# WBD_03.net
KiCad netlist of a schematic drawn in EAGLE
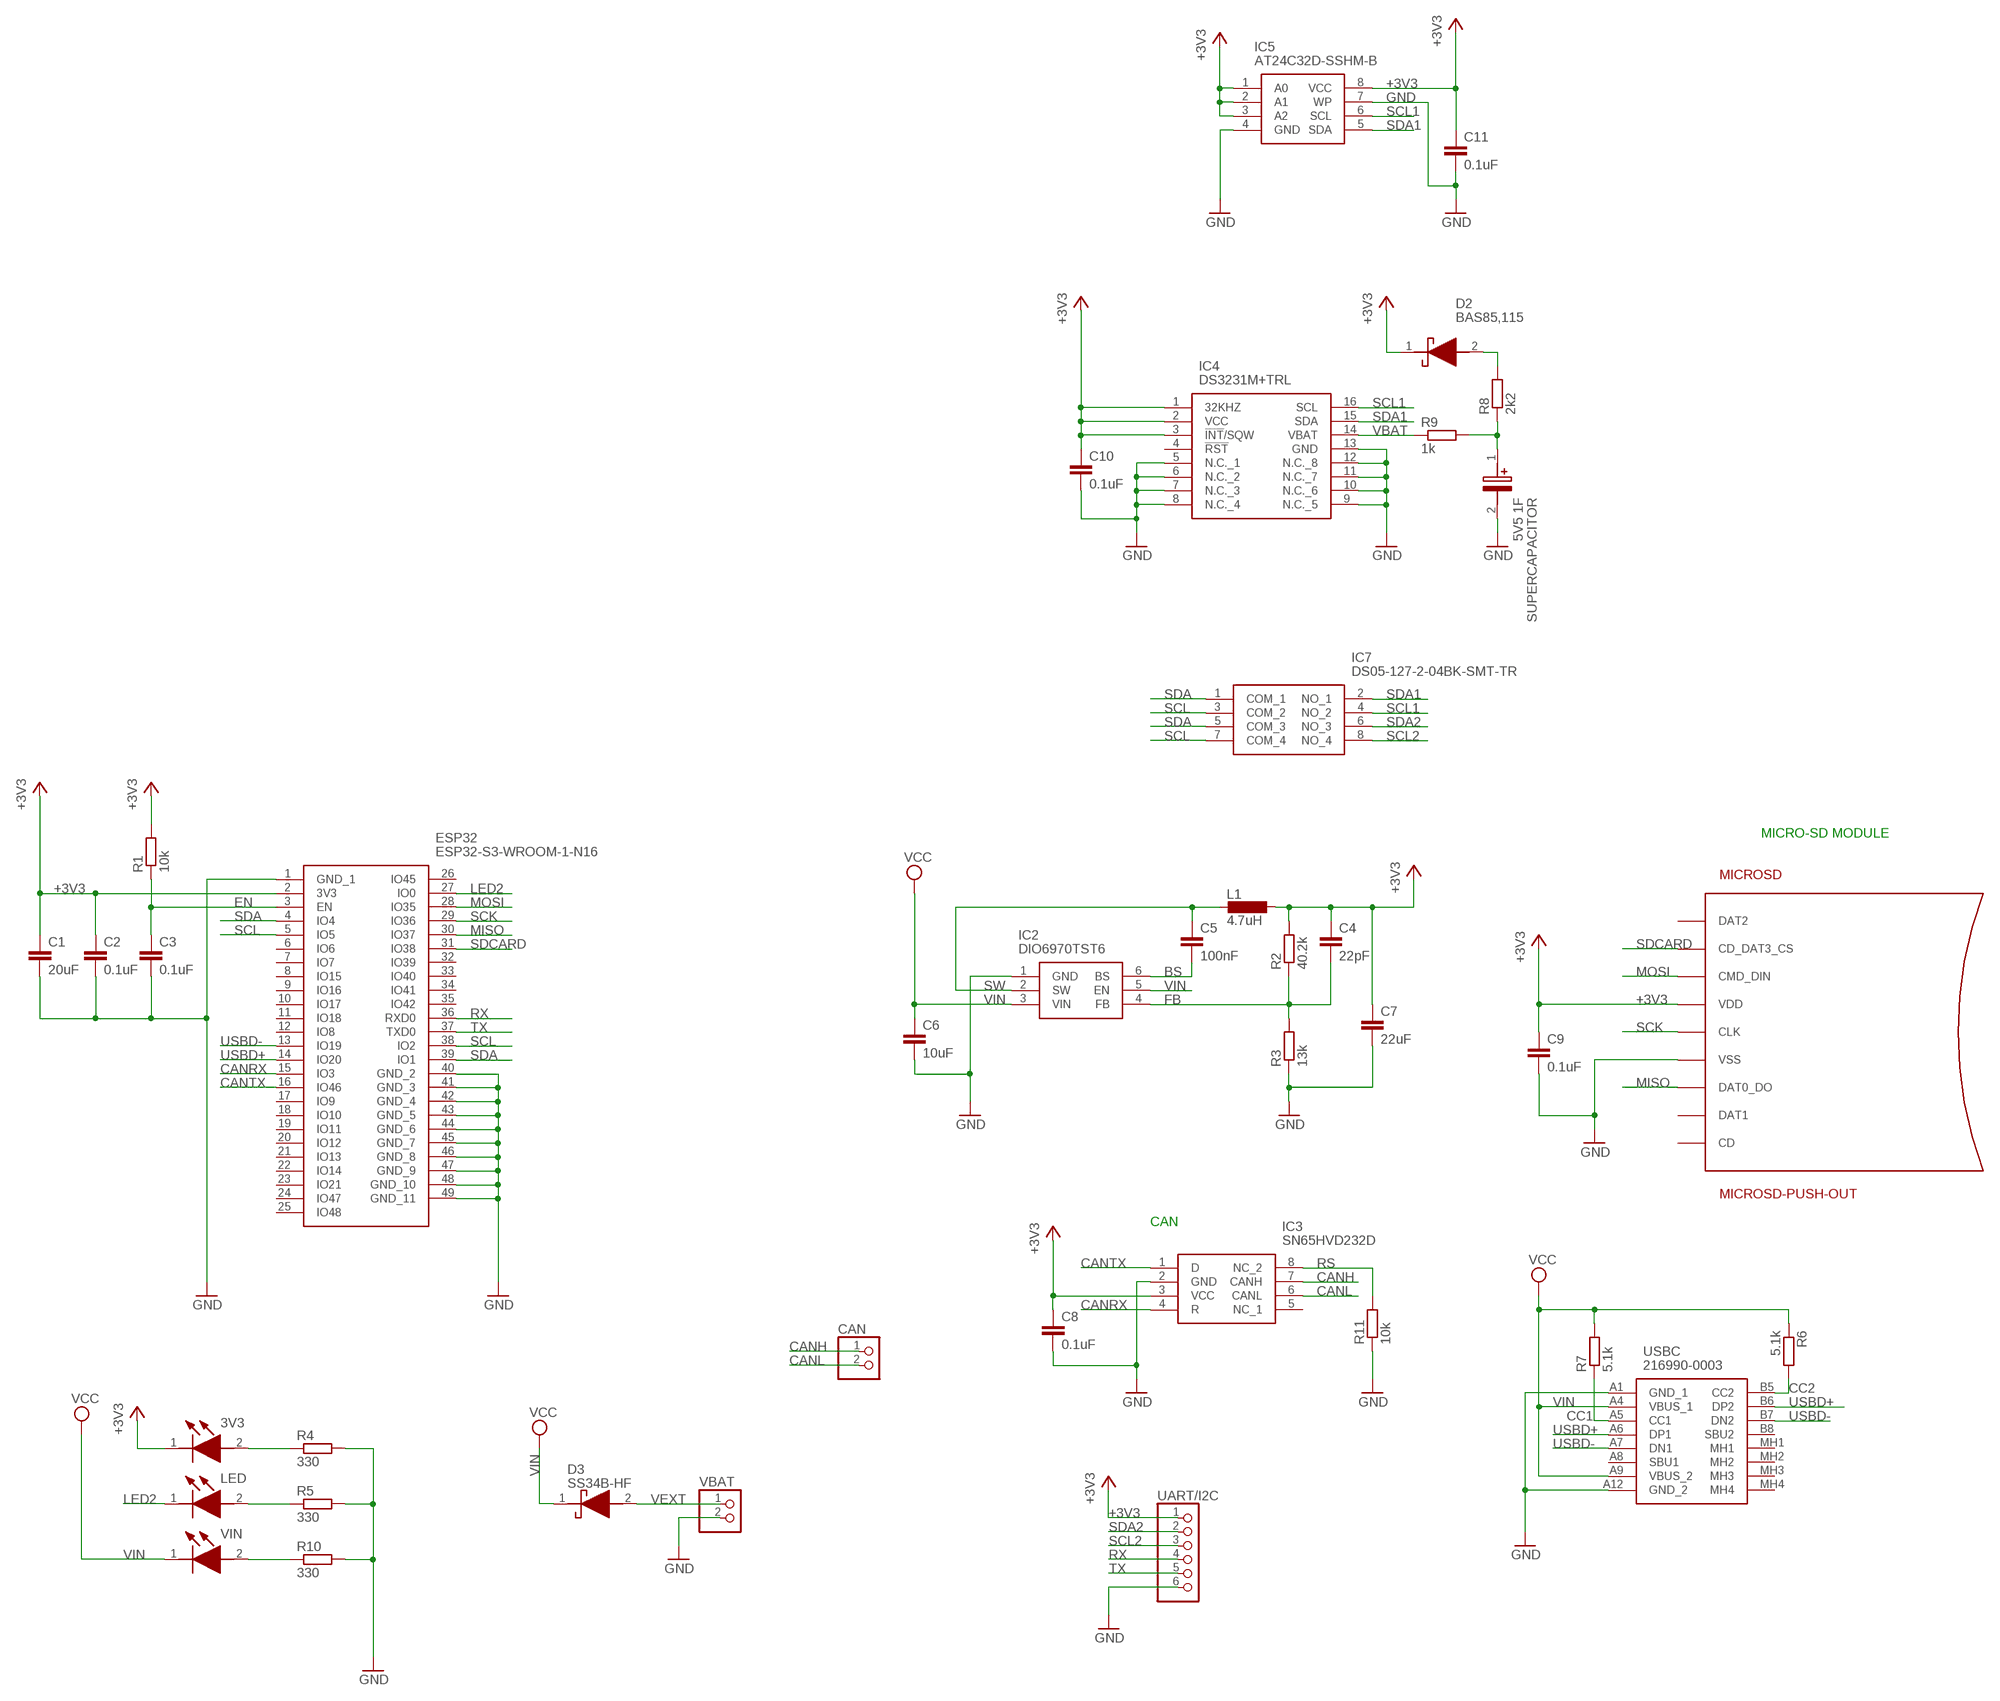
[diagram p0: schematic, sheet 1]

(export (version "E")
  (design (tool "Eeschema 10.0.6"))
  (components
    (comp (ref "3V3")
      (value "150060GS75000")
      (footprint "eagle-import:LEDC1608X80N")
      (fields (field (name "MOUSER_PART_NUMBER") "710-150060GS75000"))
      (libsource (lib "eagle-import") (part "150060GS75000"))
    )
    (comp (ref "C1")
      (value "20uF")
      (footprint "eagle-import:C0603")
      (libsource (lib "eagle-import") (part "C-EUC0603"))
    )
    (comp (ref "C2")
      (value "0.1uF")
      (footprint "eagle-import:C0603")
      (libsource (lib "eagle-import") (part "C-EUC0603"))
    )
    (comp (ref "C3")
      (value "0.1uF")
      (footprint "eagle-import:C0603")
      (libsource (lib "eagle-import") (part "C-EUC0603"))
    )
    (comp (ref "C4")
      (value "22pF")
      (footprint "eagle-import:C0603")
      (libsource (lib "eagle-import") (part "C-EUC0603"))
    )
    (comp (ref "C5")
      (value "100nF")
      (footprint "eagle-import:C0603")
      (libsource (lib "eagle-import") (part "C-EUC0603"))
    )
    (comp (ref "C6")
      (value "10uF")
      (footprint "eagle-import:C0603")
      (libsource (lib "eagle-import") (part "C-EUC0603"))
    )
    (comp (ref "C7")
      (value "22uF")
      (footprint "eagle-import:C0603")
      (libsource (lib "eagle-import") (part "C-EUC0603"))
    )
    (comp (ref "C8")
      (value "0.1uF")
      (footprint "eagle-import:C0603")
      (libsource (lib "eagle-import") (part "C-EUC0603"))
    )
    (comp (ref "C9")
      (value "0.1uF")
      (footprint "eagle-import:C0603")
      (libsource (lib "eagle-import") (part "C-EUC0603"))
    )
    (comp (ref "C10")
      (value "0.1uF")
      (footprint "eagle-import:C0603")
      (libsource (lib "eagle-import") (part "C-EUC0603"))
    )
    (comp (ref "C11")
      (value "0.1uF")
      (footprint "eagle-import:C0603")
      (libsource (lib "eagle-import") (part "C-EUC0603"))
    )
    (comp (ref "CAN")
      (value "PINHD-1X2")
      (footprint "eagle-import:1X02")
      (libsource (lib "eagle-import") (part "PINHD-1X2"))
    )
    (comp (ref "D2")
      (value "BAS85,115")
      (footprint "eagle-import:BAS85115")
      (fields (field (name "MOUSER_PART_NUMBER") "771-BAS85-T/R"))
      (libsource (lib "eagle-import") (part "BAS85,115"))
    )
    (comp (ref "D3")
      (value "SS34B-HF")
      (footprint "eagle-import:DIOM5336X320N")
      (fields (field (name "MOUSER_PART_NUMBER") "750-SS34B-HF"))
      (libsource (lib "eagle-import") (part "SS34B-HF"))
    )
    (comp (ref "ESP32")
      (value "ESP32-S3-WROOM-1-N16")
      (footprint "eagle-import:ESP32S3WROOM1N16")
      (fields (field (name "MOUSER_PART_NUMBER") "356-ESP32S3WROOM1N16"))
      (libsource (lib "eagle-import") (part "ESP32-S3-WROOM-1-N16"))
    )
    (comp (ref "IC2")
      (value "DIO6970TST6")
      (footprint "eagle-import:SOT95P280X90-6N")
      (fields (field (name "MOUSER_PART_NUMBER") "453-DIO6970ST6"))
      (libsource (lib "eagle-import") (part "DIO6970TST6"))
    )
    (comp (ref "IC3")
      (value "SN65HVD232D")
      (footprint "eagle-import:SOIC127P600X175-8N")
      (fields (field (name "MOUSER_PART_NUMBER") "595-SN65HVD232D"))
      (libsource (lib "eagle-import") (part "SN65HVD232D"))
    )
    (comp (ref "IC4")
      (value "DS3231M+TRL")
      (footprint "eagle-import:SOIC127P1032X265-16N")
      (fields (field (name "MOUSER_PART_NUMBER") "700-DS3231M+TRL"))
      (libsource (lib "eagle-import") (part "DS3231M+TRL"))
    )
    (comp (ref "IC5")
      (value "AT24C32D-SSHM-B")
      (footprint "eagle-import:SOIC127P600X175-8N")
      (fields (field (name "MOUSER_PART_NUMBER") "556-AT24C32D-SSHM-B"))
      (libsource (lib "eagle-import") (part "AT24C32D-SSHM-B"))
    )
    (comp (ref "IC7")
      (value "DS05-127-2-04BK-SMT-TR")
      (footprint "eagle-import:DS05127204BKSMTTR")
      (fields (field (name "MOUSER_PART_NUMBER") "490-DS05127204BK-STR"))
      (libsource (lib "eagle-import") (part "DS05-127-2-04BK-SMT-TR"))
    )
    (comp (ref "L1")
      (value "4.7uH")
      (footprint "eagle-import:L5650M")
      (libsource (lib "eagle-import") (part "L-EUL5650M"))
    )
    (comp (ref "LED")
      (value "150060GS75000")
      (footprint "eagle-import:LEDC1608X80N")
      (fields (field (name "MOUSER_PART_NUMBER") "710-150060GS75000"))
      (libsource (lib "eagle-import") (part "150060GS75000"))
    )
    (comp (ref "MICROSD")
      (value "MICROSD-PUSH-OUT")
      (footprint "eagle-import:MICROSD-PUSH-OUT")
      (libsource (lib "eagle-import") (part "MICROSD-PUSH-OUT"))
    )
    (comp (ref "R1")
      (value "10k")
      (footprint "eagle-import:R0603")
      (libsource (lib "eagle-import") (part "R-EU_R0603"))
    )
    (comp (ref "R2")
      (value "40.2k")
      (footprint "eagle-import:R0603")
      (libsource (lib "eagle-import") (part "R-EU_R0603"))
    )
    (comp (ref "R3")
      (value "13k")
      (footprint "eagle-import:R0603")
      (libsource (lib "eagle-import") (part "R-EU_R0603"))
    )
    (comp (ref "R4")
      (value "330")
      (footprint "eagle-import:R0603")
      (libsource (lib "eagle-import") (part "R-EU_R0603"))
    )
    (comp (ref "R5")
      (value "330")
      (footprint "eagle-import:R0603")
      (libsource (lib "eagle-import") (part "R-EU_R0603"))
    )
    (comp (ref "R6")
      (value "5.1k")
      (footprint "eagle-import:R0603")
      (libsource (lib "eagle-import") (part "R-EU_R0603"))
    )
    (comp (ref "R7")
      (value "5.1k")
      (footprint "eagle-import:R0603")
      (libsource (lib "eagle-import") (part "R-EU_R0603"))
    )
    (comp (ref "R8")
      (value "2k2")
      (footprint "eagle-import:R0603")
      (libsource (lib "eagle-import") (part "R-EU_R0603"))
    )
    (comp (ref "R9")
      (value "1k")
      (footprint "eagle-import:R0603")
      (libsource (lib "eagle-import") (part "R-EU_R0603"))
    )
    (comp (ref "R10")
      (value "330")
      (footprint "eagle-import:R0603")
      (libsource (lib "eagle-import") (part "R-EU_R0603"))
    )
    (comp (ref "R11")
      (value "10k")
      (footprint "eagle-import:R0603")
      (libsource (lib "eagle-import") (part "R-EU_R0603"))
    )
    (comp (ref "SUPERCAPACITOR")
      (value "5V5 1F")
      (footprint "eagle-import:CAPPRD500W130D2150H800")
      (fields
        (field (name "MANUFACTURER_PART_NUMBER") "DB-5R5D105T")
        (field (name "MOUSER_PART_NUMBER") "555-DB-5R5D105T")
      )
      (libsource (lib "eagle-import") (part "DB-5R5D105T"))
    )
    (comp (ref "UART/I2C")
      (value "PINHD-1X6")
      (footprint "eagle-import:1X06")
      (libsource (lib "eagle-import") (part "PINHD-1X6"))
    )
    (comp (ref "USBC")
      (value "216990-0003")
      (footprint "eagle-import:2169900003")
      (fields (field (name "MOUSER_PART_NUMBER") "538-216990-0003"))
      (libsource (lib "eagle-import") (part "216990-0003"))
    )
    (comp (ref "VBAT")
      (value "PINHD-1X2")
      (footprint "eagle-import:1X02")
      (libsource (lib "eagle-import") (part "PINHD-1X2"))
    )
    (comp (ref "VIN")
      (value "150060GS75000")
      (footprint "eagle-import:LEDC1608X80N")
      (fields (field (name "MOUSER_PART_NUMBER") "710-150060GS75000"))
      (libsource (lib "eagle-import") (part "150060GS75000"))
    )
  )
  (nets
    (net (code "1") (name "+3V3") (class "Default")
      (node (ref "3V3") (pin "1") (pinfunction "K_1") (pintype "bidirectional"))
      (node (ref "C1") (pin "1") (pinfunction "1_1") (pintype "passive"))
      (node (ref "C10") (pin "1") (pinfunction "1_1") (pintype "passive"))
      (node (ref "C11") (pin "1") (pinfunction "1_1") (pintype "passive"))
      (node (ref "C2") (pin "1") (pinfunction "1_1") (pintype "passive"))
      (node (ref "C4") (pin "1") (pinfunction "1_1") (pintype "passive"))
      (node (ref "C7") (pin "1") (pinfunction "1_1") (pintype "passive"))
      (node (ref "C8") (pin "1") (pinfunction "1_1") (pintype "passive"))
      (node (ref "C9") (pin "1") (pinfunction "1_1") (pintype "passive"))
      (node (ref "D2") (pin "1") (pinfunction "K_1") (pintype "bidirectional"))
      (node (ref "ESP32") (pin "2") (pinfunction "3V3_2") (pintype "bidirectional"))
      (node (ref "IC3") (pin "3") (pinfunction "VCC_3") (pintype "bidirectional"))
      (node (ref "IC4") (pin "1") (pinfunction "32KHZ_1") (pintype "bidirectional"))
      (node (ref "IC4") (pin "2") (pinfunction "VCC_2") (pintype "bidirectional"))
      (node (ref "IC4") (pin "3") (pinfunction "~{INT}/SQW_3") (pintype "bidirectional"))
      (node (ref "IC5") (pin "1") (pinfunction "A0_1") (pintype "bidirectional"))
      (node (ref "IC5") (pin "2") (pinfunction "A1_2") (pintype "bidirectional"))
      (node (ref "IC5") (pin "3") (pinfunction "A2_3") (pintype "bidirectional"))
      (node (ref "IC5") (pin "8") (pinfunction "VCC_8") (pintype "bidirectional"))
      (node (ref "L1") (pin "1") (pinfunction "1_1") (pintype "passive"))
      (node (ref "MICROSD") (pin "4") (pinfunction "VDD_4") (pintype "bidirectional"))
      (node (ref "R1") (pin "2") (pinfunction "2_2") (pintype "passive"))
      (node (ref "R2") (pin "2") (pinfunction "2_2") (pintype "passive"))
      (node (ref "UART/I2C") (pin "1") (pinfunction "1_1") (pintype "passive"))
    )
    (net (code "2") (name "/BS") (class "Default")
      (node (ref "C5") (pin "2") (pinfunction "2_2") (pintype "passive"))
      (node (ref "IC2") (pin "6") (pinfunction "BS_6") (pintype "bidirectional"))
    )
    (net (code "3") (name "/CANH") (class "Default")
      (node (ref "CAN") (pin "1") (pinfunction "1_1") (pintype "passive"))
      (node (ref "IC3") (pin "7") (pinfunction "CANH_7") (pintype "bidirectional"))
    )
    (net (code "4") (name "/CANL") (class "Default")
      (node (ref "CAN") (pin "2") (pinfunction "2_2") (pintype "passive"))
      (node (ref "IC3") (pin "6") (pinfunction "CANL_6") (pintype "bidirectional"))
    )
    (net (code "5") (name "/CANRX") (class "Default")
      (node (ref "ESP32") (pin "15") (pinfunction "IO3_15") (pintype "bidirectional"))
      (node (ref "IC3") (pin "4") (pinfunction "R_4") (pintype "bidirectional"))
    )
    (net (code "6") (name "/CANTX") (class "Default")
      (node (ref "ESP32") (pin "16") (pinfunction "IO46_16") (pintype "bidirectional"))
      (node (ref "IC3") (pin "1") (pinfunction "D_1") (pintype "bidirectional"))
    )
    (net (code "7") (name "/CC1") (class "Default")
      (node (ref "R7") (pin "1") (pinfunction "1_1") (pintype "passive"))
      (node (ref "USBC") (pin "A5") (pinfunction "CC1_A5") (pintype "bidirectional"))
    )
    (net (code "8") (name "/CC2") (class "Default")
      (node (ref "R6") (pin "2") (pinfunction "2_2") (pintype "passive"))
      (node (ref "USBC") (pin "B5") (pinfunction "CC2_B5") (pintype "bidirectional"))
    )
    (net (code "9") (name "/EN") (class "Default")
      (node (ref "C3") (pin "1") (pinfunction "1_1") (pintype "passive"))
      (node (ref "ESP32") (pin "3") (pinfunction "EN_3") (pintype "bidirectional"))
      (node (ref "R1") (pin "1") (pinfunction "1_1") (pintype "passive"))
    )
    (net (code "10") (name "/FB") (class "Default")
      (node (ref "C4") (pin "2") (pinfunction "2_2") (pintype "passive"))
      (node (ref "IC2") (pin "4") (pinfunction "FB_4") (pintype "bidirectional"))
      (node (ref "R2") (pin "1") (pinfunction "1_1") (pintype "passive"))
      (node (ref "R3") (pin "2") (pinfunction "2_2") (pintype "passive"))
    )
    (net (code "11") (name "/LED2") (class "Default")
      (node (ref "ESP32") (pin "27") (pinfunction "IO0_27") (pintype "bidirectional"))
      (node (ref "LED") (pin "1") (pinfunction "K_1") (pintype "bidirectional"))
    )
    (net (code "12") (name "/MISO") (class "Default")
      (node (ref "ESP32") (pin "30") (pinfunction "IO37_30") (pintype "bidirectional"))
      (node (ref "MICROSD") (pin "7") (pinfunction "DAT0_DO_7") (pintype "bidirectional"))
    )
    (net (code "13") (name "/MOSI") (class "Default")
      (node (ref "ESP32") (pin "28") (pinfunction "IO35_28") (pintype "bidirectional"))
      (node (ref "MICROSD") (pin "3") (pinfunction "CMD_DIN_3") (pintype "bidirectional"))
    )
    (net (code "14") (name "/RS") (class "Default")
      (node (ref "IC3") (pin "8") (pinfunction "NC_2_8") (pintype "bidirectional"))
      (node (ref "R11") (pin "2") (pinfunction "2_2") (pintype "passive"))
    )
    (net (code "15") (name "/RX") (class "Default")
      (node (ref "ESP32") (pin "36") (pinfunction "RXD0_36") (pintype "bidirectional"))
      (node (ref "UART/I2C") (pin "4") (pinfunction "4_4") (pintype "passive"))
    )
    (net (code "16") (name "/SCK") (class "Default")
      (node (ref "ESP32") (pin "29") (pinfunction "IO36_29") (pintype "bidirectional"))
      (node (ref "MICROSD") (pin "5") (pinfunction "CLK_5") (pintype "bidirectional"))
    )
    (net (code "17") (name "/SCL") (class "Default")
      (node (ref "ESP32") (pin "38") (pinfunction "IO2_38") (pintype "bidirectional"))
      (node (ref "ESP32") (pin "5") (pinfunction "IO5_5") (pintype "bidirectional"))
      (node (ref "IC7") (pin "3") (pinfunction "COM_2_3") (pintype "bidirectional"))
      (node (ref "IC7") (pin "7") (pinfunction "COM_4_7") (pintype "bidirectional"))
    )
    (net (code "18") (name "/SCL1") (class "Default")
      (node (ref "IC4") (pin "16") (pinfunction "SCL_16") (pintype "bidirectional"))
      (node (ref "IC5") (pin "6") (pinfunction "SCL_6") (pintype "bidirectional"))
      (node (ref "IC7") (pin "4") (pinfunction "NO_2_4") (pintype "bidirectional"))
    )
    (net (code "19") (name "/SCL2") (class "Default")
      (node (ref "IC7") (pin "8") (pinfunction "NO_4_8") (pintype "bidirectional"))
      (node (ref "UART/I2C") (pin "3") (pinfunction "3_3") (pintype "passive"))
    )
    (net (code "20") (name "/SDA") (class "Default")
      (node (ref "ESP32") (pin "39") (pinfunction "IO1_39") (pintype "bidirectional"))
      (node (ref "ESP32") (pin "4") (pinfunction "IO4_4") (pintype "bidirectional"))
      (node (ref "IC7") (pin "1") (pinfunction "COM_1_1") (pintype "bidirectional"))
      (node (ref "IC7") (pin "5") (pinfunction "COM_3_5") (pintype "bidirectional"))
    )
    (net (code "21") (name "/SDA1") (class "Default")
      (node (ref "IC4") (pin "15") (pinfunction "SDA_15") (pintype "bidirectional"))
      (node (ref "IC5") (pin "5") (pinfunction "SDA_5") (pintype "bidirectional"))
      (node (ref "IC7") (pin "2") (pinfunction "NO_1_2") (pintype "bidirectional"))
    )
    (net (code "22") (name "/SDA2") (class "Default")
      (node (ref "IC7") (pin "6") (pinfunction "NO_3_6") (pintype "bidirectional"))
      (node (ref "UART/I2C") (pin "2") (pinfunction "2_2") (pintype "passive"))
    )
    (net (code "23") (name "/SDCARD") (class "Default")
      (node (ref "ESP32") (pin "31") (pinfunction "IO38_31") (pintype "bidirectional"))
      (node (ref "MICROSD") (pin "2") (pinfunction "CD_DAT3_CS_2") (pintype "bidirectional"))
    )
    (net (code "24") (name "/SW") (class "Default")
      (node (ref "C5") (pin "1") (pinfunction "1_1") (pintype "passive"))
      (node (ref "IC2") (pin "2") (pinfunction "SW_2") (pintype "bidirectional"))
      (node (ref "L1") (pin "2") (pinfunction "2_2") (pintype "passive"))
    )
    (net (code "25") (name "/TX") (class "Default")
      (node (ref "ESP32") (pin "37") (pinfunction "TXD0_37") (pintype "bidirectional"))
      (node (ref "UART/I2C") (pin "5") (pinfunction "5_5") (pintype "passive"))
    )
    (net (code "26") (name "/USBD+") (class "Default")
      (node (ref "ESP32") (pin "14") (pinfunction "IO20_14") (pintype "bidirectional"))
      (node (ref "USBC") (pin "A6") (pinfunction "DP1_A6") (pintype "bidirectional"))
      (node (ref "USBC") (pin "B6") (pinfunction "DP2_B6") (pintype "bidirectional"))
    )
    (net (code "27") (name "/USBD-") (class "Default")
      (node (ref "ESP32") (pin "13") (pinfunction "IO19_13") (pintype "bidirectional"))
      (node (ref "USBC") (pin "A7") (pinfunction "DN1_A7") (pintype "bidirectional"))
      (node (ref "USBC") (pin "B7") (pinfunction "DN2_B7") (pintype "bidirectional"))
    )
    (net (code "28") (name "/VBAT") (class "Default")
      (node (ref "IC4") (pin "14") (pinfunction "VBAT_14") (pintype "bidirectional"))
      (node (ref "R9") (pin "1") (pinfunction "1_1") (pintype "passive"))
    )
    (net (code "29") (name "/VEXT") (class "Default")
      (node (ref "D3") (pin "2") (pinfunction "A_2") (pintype "bidirectional"))
      (node (ref "VBAT") (pin "1") (pinfunction "1_1") (pintype "passive"))
    )
    (net (code "30") (name "GND") (class "Default")
      (node (ref "C1") (pin "2") (pinfunction "2_2") (pintype "passive"))
      (node (ref "C10") (pin "2") (pinfunction "2_2") (pintype "passive"))
      (node (ref "C11") (pin "2") (pinfunction "2_2") (pintype "passive"))
      (node (ref "C2") (pin "2") (pinfunction "2_2") (pintype "passive"))
      (node (ref "C3") (pin "2") (pinfunction "2_2") (pintype "passive"))
      (node (ref "C6") (pin "2") (pinfunction "2_2") (pintype "passive"))
      (node (ref "C7") (pin "2") (pinfunction "2_2") (pintype "passive"))
      (node (ref "C8") (pin "2") (pinfunction "2_2") (pintype "passive"))
      (node (ref "C9") (pin "2") (pinfunction "2_2") (pintype "passive"))
      (node (ref "ESP32") (pin "1") (pinfunction "GND_1_1") (pintype "bidirectional"))
      (node (ref "ESP32") (pin "40") (pinfunction "GND_2_40") (pintype "bidirectional"))
      (node (ref "ESP32") (pin "41") (pinfunction "GND_3_41") (pintype "bidirectional"))
      (node (ref "ESP32") (pin "42") (pinfunction "GND_4_42") (pintype "bidirectional"))
      (node (ref "ESP32") (pin "43") (pinfunction "GND_5_43") (pintype "bidirectional"))
      (node (ref "ESP32") (pin "44") (pinfunction "GND_6_44") (pintype "bidirectional"))
      (node (ref "ESP32") (pin "45") (pinfunction "GND_7_45") (pintype "bidirectional"))
      (node (ref "ESP32") (pin "46") (pinfunction "GND_8_46") (pintype "bidirectional"))
      (node (ref "ESP32") (pin "47") (pinfunction "GND_9_47") (pintype "bidirectional"))
      (node (ref "ESP32") (pin "48") (pinfunction "GND_10_48") (pintype "bidirectional"))
      (node (ref "ESP32") (pin "49") (pinfunction "GND_11_49") (pintype "bidirectional"))
      (node (ref "IC2") (pin "1") (pinfunction "GND_1") (pintype "bidirectional"))
      (node (ref "IC3") (pin "2") (pinfunction "GND_2") (pintype "bidirectional"))
      (node (ref "IC4") (pin "10") (pinfunction "N.C._6_10") (pintype "bidirectional"))
      (node (ref "IC4") (pin "11") (pinfunction "N.C._7_11") (pintype "bidirectional"))
      (node (ref "IC4") (pin "12") (pinfunction "N.C._8_12") (pintype "bidirectional"))
      (node (ref "IC4") (pin "13") (pinfunction "GND_13") (pintype "bidirectional"))
      (node (ref "IC4") (pin "5") (pinfunction "N.C._1_5") (pintype "bidirectional"))
      (node (ref "IC4") (pin "6") (pinfunction "N.C._2_6") (pintype "bidirectional"))
      (node (ref "IC4") (pin "7") (pinfunction "N.C._3_7") (pintype "bidirectional"))
      (node (ref "IC4") (pin "8") (pinfunction "N.C._4_8") (pintype "bidirectional"))
      (node (ref "IC4") (pin "9") (pinfunction "N.C._5_9") (pintype "bidirectional"))
      (node (ref "IC5") (pin "4") (pinfunction "GND_4") (pintype "bidirectional"))
      (node (ref "IC5") (pin "7") (pinfunction "WP_7") (pintype "bidirectional"))
      (node (ref "MICROSD") (pin "6") (pinfunction "VSS_6") (pintype "bidirectional"))
      (node (ref "MICROSD") (pin "G1") (pinfunction "VSS_G1") (pintype "bidirectional"))
      (node (ref "MICROSD") (pin "G2") (pinfunction "VSS_G2") (pintype "bidirectional"))
      (node (ref "MICROSD") (pin "G3") (pinfunction "VSS_G3") (pintype "bidirectional"))
      (node (ref "MICROSD") (pin "G4") (pinfunction "VSS_G4") (pintype "bidirectional"))
      (node (ref "R10") (pin "2") (pinfunction "2_2") (pintype "passive"))
      (node (ref "R11") (pin "1") (pinfunction "1_1") (pintype "passive"))
      (node (ref "R3") (pin "1") (pinfunction "1_1") (pintype "passive"))
      (node (ref "R4") (pin "2") (pinfunction "2_2") (pintype "passive"))
      (node (ref "R5") (pin "2") (pinfunction "2_2") (pintype "passive"))
      (node (ref "SUPERCAPACITOR") (pin "2") (pinfunction "-_2") (pintype "bidirectional"))
      (node (ref "UART/I2C") (pin "6") (pinfunction "6_6") (pintype "passive"))
      (node (ref "USBC") (pin "A1") (pinfunction "GND_1_A1") (pintype "bidirectional"))
      (node (ref "USBC") (pin "A12") (pinfunction "GND_2_A12") (pintype "bidirectional"))
      (node (ref "VBAT") (pin "2") (pinfunction "2_2") (pintype "passive"))
    )
    (net (code "31") (name "Net-(3V3-A)") (class "Default")
      (node (ref "3V3") (pin "2") (pinfunction "A_2") (pintype "bidirectional"))
      (node (ref "R4") (pin "1") (pinfunction "1_1") (pintype "passive"))
    )
    (net (code "32") (name "Net-(D2-A)") (class "Default")
      (node (ref "D2") (pin "2") (pinfunction "A_2") (pintype "bidirectional"))
      (node (ref "R8") (pin "2") (pinfunction "2_2") (pintype "passive"))
    )
    (net (code "33") (name "Net-(LED-A)") (class "Default")
      (node (ref "LED") (pin "2") (pinfunction "A_2") (pintype "bidirectional"))
      (node (ref "R5") (pin "1") (pinfunction "1_1") (pintype "passive"))
    )
    (net (code "34") (name "Net-(SUPERCAPACITOR-+)") (class "Default")
      (node (ref "R8") (pin "1") (pinfunction "1_1") (pintype "passive"))
      (node (ref "R9") (pin "2") (pinfunction "2_2") (pintype "passive"))
      (node (ref "SUPERCAPACITOR") (pin "1") (pinfunction "+_1") (pintype "bidirectional"))
    )
    (net (code "35") (name "Net-(VIN-A)") (class "Default")
      (node (ref "R10") (pin "1") (pinfunction "1_1") (pintype "passive"))
      (node (ref "VIN") (pin "2") (pinfunction "A_2") (pintype "bidirectional"))
    )
    (net (code "36") (name "VCC") (class "Default")
      (node (ref "C6") (pin "1") (pinfunction "1_1") (pintype "passive"))
      (node (ref "D3") (pin "1") (pinfunction "K_1") (pintype "bidirectional"))
      (node (ref "IC2") (pin "3") (pinfunction "VIN_3") (pintype "bidirectional"))
      (node (ref "IC2") (pin "5") (pinfunction "EN_5") (pintype "bidirectional"))
      (node (ref "R6") (pin "1") (pinfunction "1_1") (pintype "passive"))
      (node (ref "R7") (pin "2") (pinfunction "2_2") (pintype "passive"))
      (node (ref "USBC") (pin "A4") (pinfunction "VBUS_1_A4") (pintype "bidirectional"))
      (node (ref "USBC") (pin "A9") (pinfunction "VBUS_2_A9") (pintype "bidirectional"))
      (node (ref "VIN") (pin "1") (pinfunction "K_1") (pintype "bidirectional"))
    )
    (net (code "37") (name "unconnected-(ESP32-IO6-Pad6)") (class "Default")
      (node (ref "ESP32") (pin "6") (pinfunction "IO6_6") (pintype "bidirectional"))
    )
    (net (code "38") (name "unconnected-(ESP32-IO7-Pad7)") (class "Default")
      (node (ref "ESP32") (pin "7") (pinfunction "IO7_7") (pintype "bidirectional"))
    )
    (net (code "39") (name "unconnected-(ESP32-IO8-Pad12)") (class "Default")
      (node (ref "ESP32") (pin "12") (pinfunction "IO8_12") (pintype "bidirectional"))
    )
    (net (code "40") (name "unconnected-(ESP32-IO9-Pad17)") (class "Default")
      (node (ref "ESP32") (pin "17") (pinfunction "IO9_17") (pintype "bidirectional"))
    )
    (net (code "41") (name "unconnected-(ESP32-IO10-Pad18)") (class "Default")
      (node (ref "ESP32") (pin "18") (pinfunction "IO10_18") (pintype "bidirectional"))
    )
    (net (code "42") (name "unconnected-(ESP32-IO11-Pad19)") (class "Default")
      (node (ref "ESP32") (pin "19") (pinfunction "IO11_19") (pintype "bidirectional"))
    )
    (net (code "43") (name "unconnected-(ESP32-IO12-Pad20)") (class "Default")
      (node (ref "ESP32") (pin "20") (pinfunction "IO12_20") (pintype "bidirectional"))
    )
    (net (code "44") (name "unconnected-(ESP32-IO13-Pad21)") (class "Default")
      (node (ref "ESP32") (pin "21") (pinfunction "IO13_21") (pintype "bidirectional"))
    )
    (net (code "45") (name "unconnected-(ESP32-IO14-Pad22)") (class "Default")
      (node (ref "ESP32") (pin "22") (pinfunction "IO14_22") (pintype "bidirectional"))
    )
    (net (code "46") (name "unconnected-(ESP32-IO15-Pad8)") (class "Default")
      (node (ref "ESP32") (pin "8") (pinfunction "IO15_8") (pintype "bidirectional"))
    )
    (net (code "47") (name "unconnected-(ESP32-IO16-Pad9)") (class "Default")
      (node (ref "ESP32") (pin "9") (pinfunction "IO16_9") (pintype "bidirectional"))
    )
    (net (code "48") (name "unconnected-(ESP32-IO17-Pad10)") (class "Default")
      (node (ref "ESP32") (pin "10") (pinfunction "IO17_10") (pintype "bidirectional"))
    )
    (net (code "49") (name "unconnected-(ESP32-IO18-Pad11)") (class "Default")
      (node (ref "ESP32") (pin "11") (pinfunction "IO18_11") (pintype "bidirectional"))
    )
    (net (code "50") (name "unconnected-(ESP32-IO21-Pad23)") (class "Default")
      (node (ref "ESP32") (pin "23") (pinfunction "IO21_23") (pintype "bidirectional"))
    )
    (net (code "51") (name "unconnected-(ESP32-IO39-Pad32)") (class "Default")
      (node (ref "ESP32") (pin "32") (pinfunction "IO39_32") (pintype "bidirectional"))
    )
    (net (code "52") (name "unconnected-(ESP32-IO40-Pad33)") (class "Default")
      (node (ref "ESP32") (pin "33") (pinfunction "IO40_33") (pintype "bidirectional"))
    )
    (net (code "53") (name "unconnected-(ESP32-IO41-Pad34)") (class "Default")
      (node (ref "ESP32") (pin "34") (pinfunction "IO41_34") (pintype "bidirectional"))
    )
    (net (code "54") (name "unconnected-(ESP32-IO42-Pad35)") (class "Default")
      (node (ref "ESP32") (pin "35") (pinfunction "IO42_35") (pintype "bidirectional"))
    )
    (net (code "55") (name "unconnected-(ESP32-IO45-Pad26)") (class "Default")
      (node (ref "ESP32") (pin "26") (pinfunction "IO45_26") (pintype "bidirectional"))
    )
    (net (code "56") (name "unconnected-(ESP32-IO47-Pad24)") (class "Default")
      (node (ref "ESP32") (pin "24") (pinfunction "IO47_24") (pintype "bidirectional"))
    )
    (net (code "57") (name "unconnected-(ESP32-IO48-Pad25)") (class "Default")
      (node (ref "ESP32") (pin "25") (pinfunction "IO48_25") (pintype "bidirectional"))
    )
    (net (code "58") (name "unconnected-(IC3-NC_1-Pad5)") (class "Default")
      (node (ref "IC3") (pin "5") (pinfunction "NC_1_5") (pintype "bidirectional"))
    )
    (net (code "59") (name "unconnected-(IC4-~{RST}-Pad4)") (class "Default")
      (node (ref "IC4") (pin "4") (pinfunction "~{RST}_4") (pintype "bidirectional"))
    )
    (net (code "60") (name "unconnected-(MICROSD-DAT1-Pad8)") (class "Default")
      (node (ref "MICROSD") (pin "8") (pinfunction "DAT1_8") (pintype "bidirectional"))
    )
    (net (code "61") (name "unconnected-(MICROSD-DAT2-Pad1)") (class "Default")
      (node (ref "MICROSD") (pin "1") (pinfunction "DAT2_1") (pintype "bidirectional"))
    )
    (net (code "62") (name "unconnected-(MICROSD-PadCD)") (class "Default")
      (node (ref "MICROSD") (pin "CD") (pinfunction "CD_CD") (pintype "bidirectional"))
    )
    (net (code "63") (name "unconnected-(USBC-PadMH1)") (class "Default")
      (node (ref "USBC") (pin "MH1") (pinfunction "MH1_MH1") (pintype "bidirectional"))
    )
    (net (code "64") (name "unconnected-(USBC-PadMH2)") (class "Default")
      (node (ref "USBC") (pin "MH2") (pinfunction "MH2_MH2") (pintype "bidirectional"))
    )
    (net (code "65") (name "unconnected-(USBC-PadMH3)") (class "Default")
      (node (ref "USBC") (pin "MH3") (pinfunction "MH3_MH3") (pintype "bidirectional"))
    )
    (net (code "66") (name "unconnected-(USBC-PadMH4)") (class "Default")
      (node (ref "USBC") (pin "MH4") (pinfunction "MH4_MH4") (pintype "bidirectional"))
    )
    (net (code "67") (name "unconnected-(USBC-SBU1-PadA8)") (class "Default")
      (node (ref "USBC") (pin "A8") (pinfunction "SBU1_A8") (pintype "bidirectional"))
    )
    (net (code "68") (name "unconnected-(USBC-SBU2-PadB8)") (class "Default")
      (node (ref "USBC") (pin "B8") (pinfunction "SBU2_B8") (pintype "bidirectional"))
    )
  )
)
